# motherpetit.net
KiCad netlist of a schematic drawn in Altium Designer
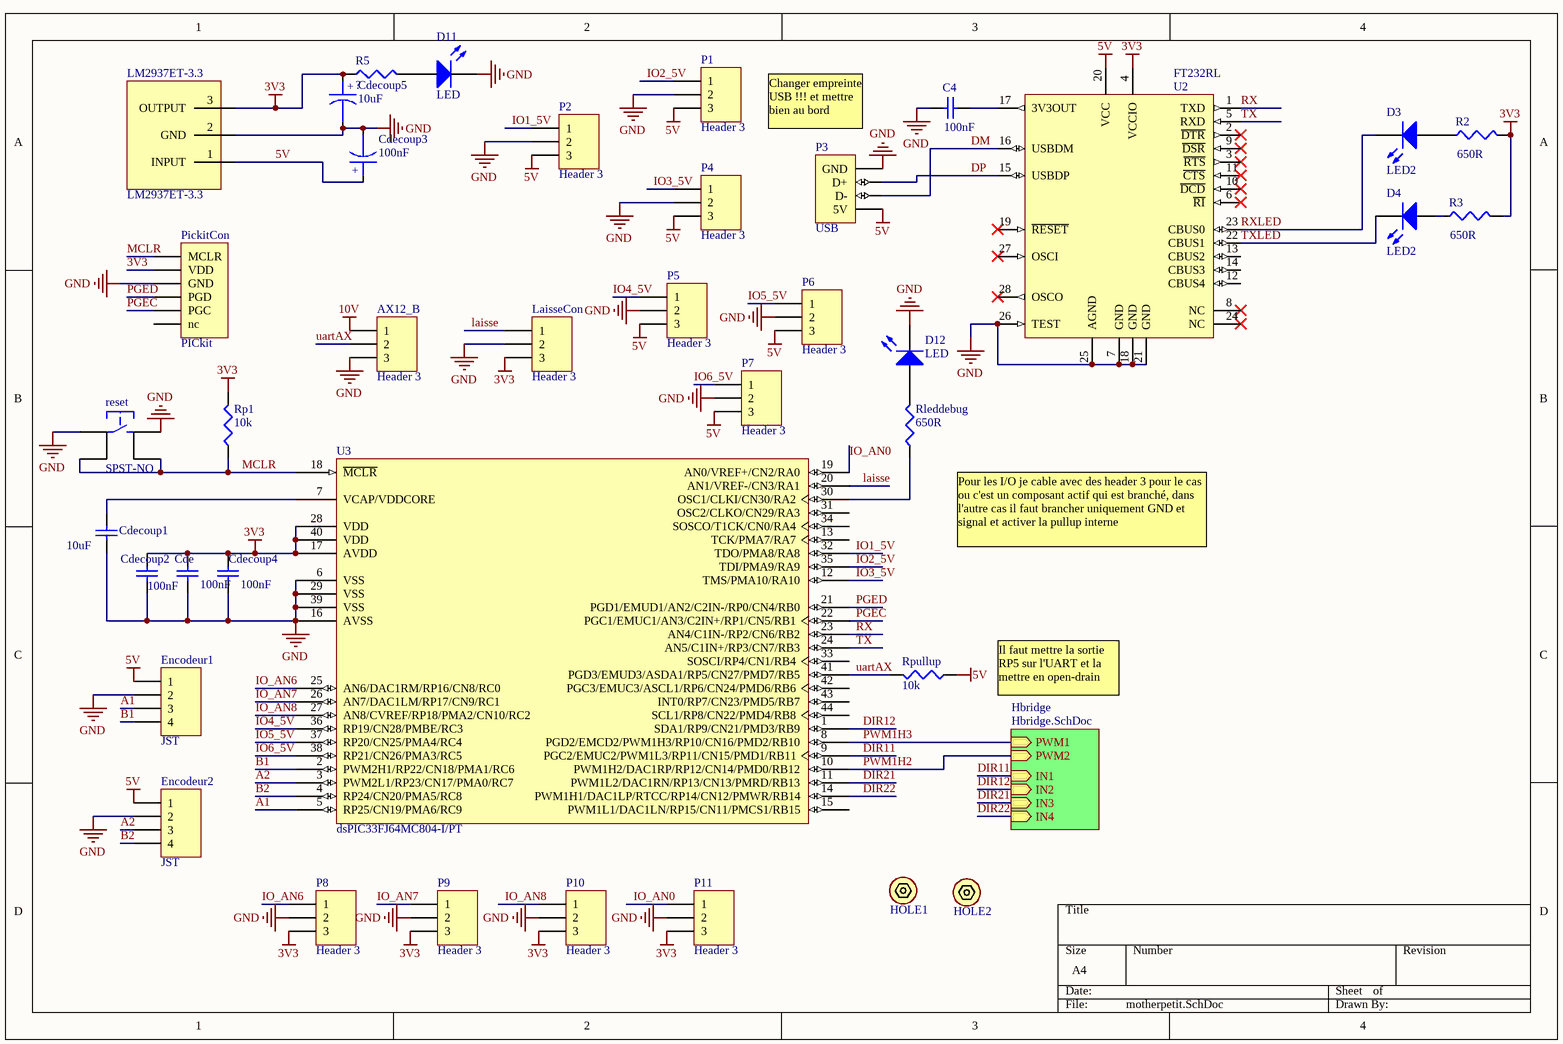
[diagram p0: motherpetit.SchDoc]

(export (version "E")
  (design (tool "Eeschema 10.0.6"))
  (components
    (comp (ref "AX12_B")
      (value "Header 3")
      (footprint "HDR1X3")
      (description "Header, 3-Pin")
      (fields (field (name "PUBLISHER") "Altium Limited"))
      (libsource (lib "7Robot") (part "Header 3"))
    )
    (comp (ref "C4")
      (value "100nF")
      (footprint "C0805C")
      (description "Capacitor (Semiconductor SIM Model)")
      (fields (field (name "PUBLISHER") "Altium Limited"))
      (libsource (lib "Miscellaneous Devices") (part "Cap Semi"))
    )
    (comp (ref "Cde")
      (value "100nF")
      (footprint "C0805C")
      (description "Capacitor")
      (fields (field (name "Comment") "CAP") (field (name "PUBLISHER") "Altium Limited"))
      (libsource (lib "7Robot") (part "CAP"))
    )
    (comp (ref "Cdecoup1")
      (value "10uF")
      (footprint "C0805C")
      (description "Capacitor")
      (fields (field (name "Comment") "CAP") (field (name "PUBLISHER") "Altium Limited"))
      (libsource (lib "7Robot") (part "CAP"))
    )
    (comp (ref "Cdecoup2")
      (value "100nF")
      (footprint "C0805C")
      (description "Capacitor")
      (fields (field (name "Comment") "CAP") (field (name "PUBLISHER") "Altium Limited"))
      (libsource (lib "7Robot") (part "CAP"))
    )
    (comp (ref "Cdecoup3")
      (value "100nF")
      (footprint "RB.1/.3")
      (description "Polarized Capacitor")
      (fields (field (name "Comment") "CAP Pol"))
      (libsource (lib "7Robot") (part "CAP Pol"))
    )
    (comp (ref "Cdecoup4")
      (value "100nF")
      (footprint "C0805C")
      (description "Capacitor")
      (fields (field (name "Comment") "CAP") (field (name "PUBLISHER") "Altium Limited"))
      (libsource (lib "7Robot") (part "CAP"))
    )
    (comp (ref "Cdecoup5")
      (value "10uF")
      (footprint "RB.1/.3")
      (description "Polarized Capacitor")
      (fields (field (name "Comment") "CAP Pol"))
      (libsource (lib "7Robot") (part "CAP Pol"))
    )
    (comp (ref "D3")
      (value "LED2")
      (footprint "LED1206Y")
      (description "Typical RED, GREEN, YELLOW, AMBER GaAs LED")
      (fields (field (name "PUBLISHER") "Altium Limited"))
      (libsource (lib "7Robot") (part "LED2"))
    )
    (comp (ref "D4")
      (value "LED2")
      (footprint "LED1206Y")
      (description "Typical RED, GREEN, YELLOW, AMBER GaAs LED")
      (fields (field (name "PUBLISHER") "Altium Limited"))
      (libsource (lib "7Robot") (part "LED2"))
    )
    (comp (ref "D11")
      (value "LED")
      (footprint "LED1206R")
      (description "Typical LED")
      (fields (field (name "PUBLISHER") "Altium Limited"))
      (libsource (lib "7Robot") (part "LED"))
    )
    (comp (ref "D12")
      (value "LED")
      (footprint "LED1206G")
      (description "Typical LED")
      (fields (field (name "PUBLISHER") "Altium Limited"))
      (libsource (lib "7Robot") (part "LED"))
    )
    (comp (ref "Encodeur1")
      (value "JST")
      (footprint "B4B-PH-K-S")
      (description "Header, 4-Pin")
      (fields (field (name "PUBLISHER") "Altium Limited"))
      (libsource (lib "Miscellaneous Connectors") (part "Header 4"))
    )
    (comp (ref "Encodeur2")
      (value "JST")
      (footprint "B4B-PH-K-S")
      (description "Header, 4-Pin")
      (fields (field (name "PUBLISHER") "Altium Limited"))
      (libsource (lib "Miscellaneous Connectors") (part "Header 4"))
    )
    (comp (ref "HOLE1")
      (value "Hole")
      (footprint "SCREW")
      (description "Mounting Hole for screws")
      (libsource (lib "7Robot") (part "Hole"))
    )
    (comp (ref "HOLE2")
      (value "Hole")
      (footprint "SCREW")
      (description "Mounting Hole for screws")
      (libsource (lib "7Robot") (part "Hole"))
    )
    (comp (ref "LaisseCon")
      (value "Header 3")
      (footprint "HDR1X3")
      (description "Header, 3-Pin")
      (fields (field (name "PUBLISHER") "Altium Limited"))
      (libsource (lib "7Robot") (part "Header 3"))
    )
    (comp (ref "LM2937ET-3.3")
      (value "LM2937ET-3.3")
      (footprint "TO-220V")
      (description "3.3V linear Regulator")
      (libsource (lib "LM293733") (part "LM2937ET-3.3"))
    )
    (comp (ref "P1")
      (value "Header 3")
      (footprint "HDR1X3")
      (description "Header, 3-Pin")
      (fields (field (name "PUBLISHER") "Altium Limited"))
      (libsource (lib "7Robot") (part "Header 3"))
    )
    (comp (ref "P2")
      (value "Header 3")
      (footprint "HDR1X3")
      (description "Header, 3-Pin")
      (fields (field (name "PUBLISHER") "Altium Limited"))
      (libsource (lib "7Robot") (part "Header 3"))
    )
    (comp (ref "P3")
      (value "USB")
      (footprint "USB/SM0.8-4H5")
      (description "USB Connector")
      (fields (field (name "PUBLISHER") "Altium Limited"))
      (libsource (lib "7Robot") (part "USB Con"))
    )
    (comp (ref "P4")
      (value "Header 3")
      (footprint "HDR1X3")
      (description "Header, 3-Pin")
      (fields (field (name "PUBLISHER") "Altium Limited"))
      (libsource (lib "7Robot") (part "Header 3"))
    )
    (comp (ref "P5")
      (value "Header 3")
      (footprint "HDR1X3")
      (description "Header, 3-Pin")
      (fields (field (name "PUBLISHER") "Altium Limited"))
      (libsource (lib "7Robot") (part "Header 3"))
    )
    (comp (ref "P6")
      (value "Header 3")
      (footprint "HDR1X3")
      (description "Header, 3-Pin")
      (fields (field (name "PUBLISHER") "Altium Limited"))
      (libsource (lib "7Robot") (part "Header 3"))
    )
    (comp (ref "P7")
      (value "Header 3")
      (footprint "HDR1X3")
      (description "Header, 3-Pin")
      (fields (field (name "PUBLISHER") "Altium Limited"))
      (libsource (lib "7Robot") (part "Header 3"))
    )
    (comp (ref "P8")
      (value "Header 3")
      (footprint "HDR1X3")
      (description "Header, 3-Pin")
      (fields (field (name "PUBLISHER") "Altium Limited"))
      (libsource (lib "7Robot") (part "Header 3"))
    )
    (comp (ref "P9")
      (value "Header 3")
      (footprint "HDR1X3")
      (description "Header, 3-Pin")
      (fields (field (name "PUBLISHER") "Altium Limited"))
      (libsource (lib "7Robot") (part "Header 3"))
    )
    (comp (ref "P10")
      (value "Header 3")
      (footprint "HDR1X3")
      (description "Header, 3-Pin")
      (fields (field (name "PUBLISHER") "Altium Limited"))
      (libsource (lib "7Robot") (part "Header 3"))
    )
    (comp (ref "P11")
      (value "Header 3")
      (footprint "HDR1X3")
      (description "Header, 3-Pin")
      (fields (field (name "PUBLISHER") "Altium Limited"))
      (libsource (lib "7Robot") (part "Header 3"))
    )
    (comp (ref "PickitCon")
      (value "PICkit")
      (footprint "HDR1X6H")
      (description "Header, 6-Pin, Right Angle")
      (fields (field (name "PUBLISHER") "Altium Limited"))
      (libsource (lib "7Robot") (part "Header ICSP"))
    )
    (comp (ref "R2")
      (value "650R")
      (footprint "C0805R")
      (description "Resistor")
      (fields (field (name "PUBLISHER") "Altium Limited"))
      (libsource (lib "Miscellaneous Devices") (part "Res3"))
    )
    (comp (ref "R3")
      (value "650R")
      (footprint "C0805R")
      (description "Resistor")
      (fields (field (name "PUBLISHER") "Altium Limited"))
      (libsource (lib "Miscellaneous Devices") (part "Res3"))
    )
    (comp (ref "R5")
      (value "?")
      (footprint "C0805R")
      (description "Resistor")
      (fields (field (name "Comment") "RES") (field (name "PUBLISHER") "Altium Limited"))
      (libsource (lib "7Robot") (part "RES"))
    )
    (comp (ref "reset")
      (value "SPST-NO")
      (footprint "SPST-NO")
      (description "Tactile Switch 7.3mm, SMD")
      (libsource (lib "7Robot") (part "SPST-NO"))
    )
    (comp (ref "Rleddebug")
      (value "650R")
      (footprint "C0805R")
      (description "Resistor")
      (fields (field (name "PUBLISHER") "Altium Limited"))
      (libsource (lib "Miscellaneous Devices") (part "Res3"))
    )
    (comp (ref "Rp1")
      (value "10k")
      (footprint "C0805R")
      (description "Resistor")
      (fields (field (name "Comment") "RES") (field (name "PUBLISHER") "Altium Limited"))
      (libsource (lib "7Robot") (part "RES"))
    )
    (comp (ref "Rpullup")
      (value "10k")
      (footprint "C0805R")
      (description "Resistor")
      (fields (field (name "Comment") "RES") (field (name "PUBLISHER") "Altium Limited"))
      (libsource (lib "7Robot") (part "RES"))
    )
    (comp (ref "U2")
      (value "FT232RL")
      (footprint "SSOP-28_M")
      (description "USB UART Asynchronous Serial Data Transfer Chip, SSOP-28, Tube")
      (fields (field (name "PUBLISHER") "Altium Limited"))
      (libsource (lib "7Robot") (part "FT232RL"))
    )
    (comp (ref "U3")
      (value "dsPIC33FJ64MC804-I/PT")
      (footprint "TQFP-PT44_N")
      (fields (field (name "PUBLISHER") "Altium Limited"))
      (libsource (lib "7Robot") (part "dsPIC33FJ64MC804-I/PT"))
    )
  )
  (nets
    (net (code "1") (name "/A1") (class "Default")
      (node (ref "Encodeur1") (pin "3") (pinfunction "3_3") (pintype "passive"))
      (node (ref "U3") (pin "5") (pinfunction "RP25/CN19/PMA6/RC9_5") (pintype "bidirectional"))
    )
    (net (code "2") (name "/A2") (class "Default")
      (node (ref "Encodeur2") (pin "3") (pinfunction "3_3") (pintype "passive"))
      (node (ref "U3") (pin "3") (pinfunction "PWM2L1/RP23/CN17/PMA0/RC7_3") (pintype "bidirectional"))
    )
    (net (code "3") (name "/B1") (class "Default")
      (node (ref "Encodeur1") (pin "4") (pinfunction "4_4") (pintype "passive"))
      (node (ref "U3") (pin "2") (pinfunction "PWM2H1/RP22/CN18/PMA1/RC6_2") (pintype "bidirectional"))
    )
    (net (code "4") (name "/B2") (class "Default")
      (node (ref "Encodeur2") (pin "4") (pinfunction "4_4") (pintype "passive"))
      (node (ref "U3") (pin "4") (pinfunction "RP24/CN20/PMA5/RC8_4") (pintype "bidirectional"))
    )
    (net (code "5") (name "/DIR11") (class "Default")
      (node (ref "U3") (pin "9") (pinfunction "PGC2/EMUC2/PWM1L3/RP11/CN15/PMD1/RB11_9") (pintype "bidirectional"))
    )
    (net (code "6") (name "/DIR12") (class "Default")
      (node (ref "U3") (pin "1") (pinfunction "SDA1/RP9/CN21/PMD3/RB9_1") (pintype "bidirectional"))
    )
    (net (code "7") (name "/DIR21") (class "Default")
      (node (ref "U3") (pin "11") (pinfunction "PWM1L2/DAC1RN/RP13/CN13/PMRD/RB13_11") (pintype "bidirectional"))
    )
    (net (code "8") (name "/DIR22") (class "Default")
      (node (ref "U3") (pin "14") (pinfunction "PWM1H1/DAC1LP/RTCC/RP14/CN12/PMWR/RB14_14") (pintype "bidirectional"))
    )
    (net (code "9") (name "/DM") (class "Default")
      (node (ref "P3") (pin "2") (pinfunction "D-_2") (pintype "bidirectional"))
      (node (ref "U2") (pin "16") (pinfunction "USBDM_16") (pintype "bidirectional"))
    )
    (net (code "10") (name "/DP") (class "Default")
      (node (ref "P3") (pin "3") (pinfunction "D+_3") (pintype "bidirectional"))
      (node (ref "U2") (pin "15") (pinfunction "USBDP_15") (pintype "bidirectional"))
    )
    (net (code "11") (name "/IO1_5V") (class "Default")
      (node (ref "P2") (pin "1") (pinfunction "1_1") (pintype "passive"))
      (node (ref "U3") (pin "32") (pinfunction "TDO/PMA8/RA8_32") (pintype "bidirectional"))
    )
    (net (code "12") (name "/IO2_5V") (class "Default")
      (node (ref "P1") (pin "1") (pinfunction "1_1") (pintype "passive"))
      (node (ref "U3") (pin "35") (pinfunction "TDI/PMA9/RA9_35") (pintype "bidirectional"))
    )
    (net (code "13") (name "/IO3_5V") (class "Default")
      (node (ref "P4") (pin "1") (pinfunction "1_1") (pintype "passive"))
      (node (ref "U3") (pin "12") (pinfunction "TMS/PMA10/RA10_12") (pintype "bidirectional"))
    )
    (net (code "14") (name "/IO4_5V") (class "Default")
      (node (ref "P5") (pin "1") (pinfunction "1_1") (pintype "passive"))
      (node (ref "U3") (pin "36") (pinfunction "RP19/CN28/PMBE/RC3_36") (pintype "bidirectional"))
    )
    (net (code "15") (name "/IO5_5V") (class "Default")
      (node (ref "P6") (pin "1") (pinfunction "1_1") (pintype "passive"))
      (node (ref "U3") (pin "37") (pinfunction "RP20/CN25/PMA4/RC4_37") (pintype "bidirectional"))
    )
    (net (code "16") (name "/IO6_5V") (class "Default")
      (node (ref "P7") (pin "1") (pinfunction "1_1") (pintype "passive"))
      (node (ref "U3") (pin "38") (pinfunction "RP21/CN26/PMA3/RC5_38") (pintype "bidirectional"))
    )
    (net (code "17") (name "/IO_AN0") (class "Default")
      (node (ref "P11") (pin "1") (pinfunction "1_1") (pintype "passive"))
      (node (ref "U3") (pin "19") (pinfunction "AN0/VREF+/CN2/RA0_19") (pintype "bidirectional"))
    )
    (net (code "18") (name "/IO_AN6") (class "Default")
      (node (ref "P8") (pin "1") (pinfunction "1_1") (pintype "passive"))
      (node (ref "U3") (pin "25") (pinfunction "AN6/DAC1RM/RP16/CN8/RC0_25") (pintype "bidirectional"))
    )
    (net (code "19") (name "/IO_AN7") (class "Default")
      (node (ref "P9") (pin "1") (pinfunction "1_1") (pintype "passive"))
      (node (ref "U3") (pin "26") (pinfunction "AN7/DAC1LM/RP17/CN9/RC1_26") (pintype "bidirectional"))
    )
    (net (code "20") (name "/IO_AN8") (class "Default")
      (node (ref "P10") (pin "1") (pinfunction "1_1") (pintype "passive"))
      (node (ref "U3") (pin "27") (pinfunction "AN8/CVREF/RP18/PMA2/CN10/RC2_27") (pintype "bidirectional"))
    )
    (net (code "21") (name "/MCLR") (class "Default")
      (node (ref "PickitCon") (pin "1") (pinfunction "MCLR_1") (pintype "passive"))
      (node (ref "Rp1") (pin "1") (pinfunction "1_1") (pintype "passive"))
      (node (ref "U3") (pin "18") (pinfunction "~{MCLR}_18") (pintype "input"))
      (node (ref "reset") (pin "2") (pintype "passive"))
      (node (ref "reset") (pin "3") (pintype "passive"))
    )
    (net (code "22") (name "/PGEC") (class "Default")
      (node (ref "PickitCon") (pin "5") (pinfunction "PGC_5") (pintype "passive"))
      (node (ref "U3") (pin "22") (pinfunction "PGC1/EMUC1/AN3/C2IN+/RP1/CN5/RB1_22") (pintype "bidirectional"))
    )
    (net (code "23") (name "/PGED") (class "Default")
      (node (ref "PickitCon") (pin "4") (pinfunction "PGD_4") (pintype "passive"))
      (node (ref "U3") (pin "21") (pinfunction "PGD1/EMUD1/AN2/C2IN-/RP0/CN4/RB0_21") (pintype "bidirectional"))
    )
    (net (code "24") (name "/PWM1H2") (class "Default")
      (node (ref "U3") (pin "10") (pinfunction "PWM1H2/DAC1RP/RP12/CN14/PMD0/RB12_10") (pintype "bidirectional"))
    )
    (net (code "25") (name "/PWM1H3") (class "Default")
      (node (ref "U3") (pin "8") (pinfunction "PGD2/EMCD2/PWM1H3/RP10/CN16/PMD2/RB10_8") (pintype "bidirectional"))
    )
    (net (code "26") (name "/RX") (class "Default")
      (node (ref "U2") (pin "1") (pinfunction "TXD_1") (pintype "output"))
      (node (ref "U3") (pin "23") (pinfunction "AN4/C1IN-/RP2/CN6/RB2_23") (pintype "bidirectional"))
    )
    (net (code "27") (name "/RXLED") (class "Default")
      (node (ref "D3") (pin "2") (pinfunction "K_2") (pintype "passive"))
      (node (ref "U2") (pin "23") (pinfunction "CBUS0_23") (pintype "bidirectional"))
    )
    (net (code "28") (name "/TX") (class "Default")
      (node (ref "U2") (pin "5") (pinfunction "RXD_5") (pintype "input"))
      (node (ref "U3") (pin "24") (pinfunction "AN5/C1IN+/RP3/CN7/RB3_24") (pintype "bidirectional"))
    )
    (net (code "29") (name "/TXLED") (class "Default")
      (node (ref "D4") (pin "2") (pinfunction "K_2") (pintype "passive"))
      (node (ref "U2") (pin "22") (pinfunction "CBUS1_22") (pintype "bidirectional"))
    )
    (net (code "30") (name "/laisse") (class "Default")
      (node (ref "LaisseCon") (pin "1") (pinfunction "1_1") (pintype "passive"))
      (node (ref "U3") (pin "20") (pinfunction "AN1/VREF-/CN3/RA1_20") (pintype "bidirectional"))
    )
    (net (code "31") (name "/uartAX") (class "Default")
      (node (ref "AX12_B") (pin "2") (pinfunction "2_2") (pintype "passive"))
      (node (ref "Rpullup") (pin "2") (pinfunction "2_2") (pintype "passive"))
      (node (ref "U3") (pin "41") (pinfunction "PGD3/EMUD3/ASDA1/RP5/CN27/PMD7/RB5_41") (pintype "bidirectional"))
    )
    (net (code "32") (name "3V3") (class "Default")
      (node (ref "Cde") (pin "2") (pinfunction "2_2") (pintype "passive"))
      (node (ref "Cdecoup2") (pin "2") (pinfunction "2_2") (pintype "passive"))
      (node (ref "Cdecoup4") (pin "2") (pinfunction "2_2") (pintype "passive"))
      (node (ref "Cdecoup5") (pin "1") (pinfunction "1_1") (pintype "passive"))
      (node (ref "LM2937ET-3.3") (pin "3") (pinfunction "OUTPUT_3") (pintype "power_in"))
      (node (ref "LaisseCon") (pin "3") (pinfunction "3_3") (pintype "passive"))
      (node (ref "P10") (pin "3") (pinfunction "3_3") (pintype "passive"))
      (node (ref "P11") (pin "3") (pinfunction "3_3") (pintype "passive"))
      (node (ref "P8") (pin "3") (pinfunction "3_3") (pintype "passive"))
      (node (ref "P9") (pin "3") (pinfunction "3_3") (pintype "passive"))
      (node (ref "PickitCon") (pin "2") (pinfunction "VDD_2") (pintype "passive"))
      (node (ref "R2") (pin "2") (pinfunction "2_2") (pintype "passive"))
      (node (ref "R3") (pin "2") (pinfunction "2_2") (pintype "passive"))
      (node (ref "R5") (pin "1") (pinfunction "1_1") (pintype "passive"))
      (node (ref "Rp1") (pin "2") (pinfunction "2_2") (pintype "passive"))
      (node (ref "U2") (pin "4") (pinfunction "VCCIO_4") (pintype "power_in"))
      (node (ref "U3") (pin "17") (pinfunction "AVDD_17") (pintype "power_in"))
      (node (ref "U3") (pin "28") (pinfunction "VDD_28") (pintype "power_in"))
      (node (ref "U3") (pin "40") (pinfunction "VDD_40") (pintype "power_in"))
    )
    (net (code "33") (name "5V") (class "Default")
      (node (ref "Cdecoup3") (pin "1") (pinfunction "1_1") (pintype "passive"))
      (node (ref "Encodeur1") (pin "1") (pinfunction "1_1") (pintype "passive"))
      (node (ref "Encodeur2") (pin "1") (pinfunction "1_1") (pintype "passive"))
      (node (ref "LM2937ET-3.3") (pin "1") (pinfunction "INPUT_1") (pintype "power_in"))
      (node (ref "P1") (pin "3") (pinfunction "3_3") (pintype "passive"))
      (node (ref "P2") (pin "3") (pinfunction "3_3") (pintype "passive"))
      (node (ref "P3") (pin "1") (pinfunction "5V_1") (pintype "power_in"))
      (node (ref "P4") (pin "3") (pinfunction "3_3") (pintype "passive"))
      (node (ref "P5") (pin "3") (pinfunction "3_3") (pintype "passive"))
      (node (ref "P6") (pin "3") (pinfunction "3_3") (pintype "passive"))
      (node (ref "P7") (pin "3") (pinfunction "3_3") (pintype "passive"))
      (node (ref "Rpullup") (pin "1") (pinfunction "1_1") (pintype "passive"))
      (node (ref "U2") (pin "20") (pinfunction "VCC_20") (pintype "power_in"))
    )
    (net (code "34") (name "10V") (class "Default")
      (node (ref "AX12_B") (pin "1") (pinfunction "1_1") (pintype "passive"))
    )
    (net (code "35") (name "GND") (class "Default")
      (node (ref "AX12_B") (pin "3") (pinfunction "3_3") (pintype "passive"))
      (node (ref "C4") (pin "1") (pinfunction "1_1") (pintype "passive"))
      (node (ref "Cde") (pin "1") (pinfunction "1_1") (pintype "passive"))
      (node (ref "Cdecoup1") (pin "1") (pinfunction "1_1") (pintype "passive"))
      (node (ref "Cdecoup2") (pin "1") (pinfunction "1_1") (pintype "passive"))
      (node (ref "Cdecoup3") (pin "2") (pinfunction "2_2") (pintype "passive"))
      (node (ref "Cdecoup4") (pin "1") (pinfunction "1_1") (pintype "passive"))
      (node (ref "Cdecoup5") (pin "2") (pinfunction "2_2") (pintype "passive"))
      (node (ref "D11") (pin "2") (pinfunction "K_2") (pintype "passive"))
      (node (ref "D12") (pin "2") (pinfunction "K_2") (pintype "passive"))
      (node (ref "Encodeur1") (pin "2") (pinfunction "2_2") (pintype "passive"))
      (node (ref "Encodeur2") (pin "2") (pinfunction "2_2") (pintype "passive"))
      (node (ref "LM2937ET-3.3") (pin "2") (pinfunction "GND_2") (pintype "passive"))
      (node (ref "LaisseCon") (pin "2") (pinfunction "2_2") (pintype "passive"))
      (node (ref "P1") (pin "2") (pinfunction "2_2") (pintype "passive"))
      (node (ref "P10") (pin "2") (pinfunction "2_2") (pintype "passive"))
      (node (ref "P11") (pin "2") (pinfunction "2_2") (pintype "passive"))
      (node (ref "P2") (pin "2") (pinfunction "2_2") (pintype "passive"))
      (node (ref "P3") (pin "4") (pinfunction "GND_4") (pintype "power_in"))
      (node (ref "P4") (pin "2") (pinfunction "2_2") (pintype "passive"))
      (node (ref "P5") (pin "2") (pinfunction "2_2") (pintype "passive"))
      (node (ref "P6") (pin "2") (pinfunction "2_2") (pintype "passive"))
      (node (ref "P7") (pin "2") (pinfunction "2_2") (pintype "passive"))
      (node (ref "P8") (pin "2") (pinfunction "2_2") (pintype "passive"))
      (node (ref "P9") (pin "2") (pinfunction "2_2") (pintype "passive"))
      (node (ref "PickitCon") (pin "3") (pinfunction "GND_3") (pintype "passive"))
      (node (ref "U2") (pin "18") (pinfunction "GND_18") (pintype "power_in"))
      (node (ref "U2") (pin "21") (pinfunction "GND_21") (pintype "power_in"))
      (node (ref "U2") (pin "25") (pinfunction "AGND_25") (pintype "power_in"))
      (node (ref "U2") (pin "26") (pinfunction "TEST_26") (pintype "input"))
      (node (ref "U2") (pin "7") (pinfunction "GND_7") (pintype "power_in"))
      (node (ref "U3") (pin "16") (pinfunction "AVSS_16") (pintype "power_in"))
      (node (ref "U3") (pin "29") (pinfunction "VSS_29") (pintype "power_in"))
      (node (ref "U3") (pin "39") (pinfunction "VSS_39") (pintype "power_in"))
      (node (ref "U3") (pin "6") (pinfunction "VSS_6") (pintype "power_in"))
      (node (ref "reset") (pin "1") (pintype "passive"))
      (node (ref "reset") (pin "4") (pintype "passive"))
    )
    (net (code "36") (name "Net-(D3-A)") (class "Default")
      (node (ref "D3") (pin "1") (pinfunction "A_1") (pintype "passive"))
      (node (ref "R2") (pin "1") (pinfunction "1_1") (pintype "passive"))
    )
    (net (code "37") (name "Net-(D4-A)") (class "Default")
      (node (ref "D4") (pin "1") (pinfunction "A_1") (pintype "passive"))
      (node (ref "R3") (pin "1") (pinfunction "1_1") (pintype "passive"))
    )
    (net (code "38") (name "Net-(D11-A)") (class "Default")
      (node (ref "D11") (pin "1") (pinfunction "A_1") (pintype "passive"))
      (node (ref "R5") (pin "2") (pinfunction "2_2") (pintype "passive"))
    )
    (net (code "39") (name "Net-(D12-A)") (class "Default")
      (node (ref "D12") (pin "1") (pinfunction "A_1") (pintype "passive"))
      (node (ref "Rleddebug") (pin "2") (pinfunction "2_2") (pintype "passive"))
    )
    (net (code "40") (name "Net-(U2-3V3OUT)") (class "Default")
      (node (ref "C4") (pin "2") (pinfunction "2_2") (pintype "passive"))
      (node (ref "U2") (pin "17") (pinfunction "3V3OUT_17") (pintype "output"))
    )
    (net (code "41") (name "Net-(U3-OSC1{slash}CLKI{slash}CN30{slash}RA2)") (class "Default")
      (node (ref "Rleddebug") (pin "1") (pinfunction "1_1") (pintype "passive"))
      (node (ref "U3") (pin "30") (pinfunction "OSC1/CLKI/CN30/RA2_30") (pintype "bidirectional"))
    )
    (net (code "42") (name "Net-(U3-VCAP{slash}VDDCORE)") (class "Default")
      (node (ref "Cdecoup1") (pin "2") (pinfunction "2_2") (pintype "passive"))
      (node (ref "U3") (pin "7") (pinfunction "VCAP/VDDCORE_7") (pintype "power_in"))
    )
    (net (code "43") (name "unconnected-(HOLE1-Hole-Pad1)") (class "Default")
      (node (ref "HOLE1") (pin "1") (pinfunction "Hole_1") (pintype "passive"))
    )
    (net (code "44") (name "unconnected-(HOLE2-Hole-Pad1)") (class "Default")
      (node (ref "HOLE2") (pin "1") (pinfunction "Hole_1") (pintype "passive"))
    )
    (net (code "45") (name "unconnected-(PickitCon-nc-Pad6)") (class "Default")
      (node (ref "PickitCon") (pin "6") (pinfunction "nc_6") (pintype "passive"))
    )
    (net (code "46") (name "unconnected-(U2-CBUS2-Pad13)") (class "Default")
      (node (ref "U2") (pin "13") (pinfunction "CBUS2_13") (pintype "bidirectional"))
    )
    (net (code "47") (name "unconnected-(U2-CBUS3-Pad14)") (class "Default")
      (node (ref "U2") (pin "14") (pinfunction "CBUS3_14") (pintype "bidirectional"))
    )
    (net (code "48") (name "unconnected-(U2-CBUS4-Pad12)") (class "Default")
      (node (ref "U2") (pin "12") (pinfunction "CBUS4_12") (pintype "bidirectional"))
    )
    (net (code "49") (name "unconnected-(U2-NC-Pad8)") (class "Default")
      (node (ref "U2") (pin "8") (pinfunction "NC_8") (pintype "passive+no_connect"))
    )
    (net (code "50") (name "unconnected-(U2-NC-Pad24)") (class "Default")
      (node (ref "U2") (pin "24") (pinfunction "NC_24") (pintype "passive+no_connect"))
    )
    (net (code "51") (name "unconnected-(U2-OSCI-Pad27)") (class "Default")
      (node (ref "U2") (pin "27") (pinfunction "OSCI_27") (pintype "input+no_connect"))
    )
    (net (code "52") (name "unconnected-(U2-OSCO-Pad28)") (class "Default")
      (node (ref "U2") (pin "28") (pinfunction "OSCO_28") (pintype "output+no_connect"))
    )
    (net (code "53") (name "unconnected-(U2-~{CTS}-Pad11)") (class "Default")
      (node (ref "U2") (pin "11") (pinfunction "~{CTS}_11") (pintype "input+no_connect"))
    )
    (net (code "54") (name "unconnected-(U2-~{DCD}-Pad10)") (class "Default")
      (node (ref "U2") (pin "10") (pinfunction "~{DCD}_10") (pintype "input+no_connect"))
    )
    (net (code "55") (name "unconnected-(U2-~{DSR}-Pad9)") (class "Default")
      (node (ref "U2") (pin "9") (pinfunction "~{DSR}_9") (pintype "input+no_connect"))
    )
    (net (code "56") (name "unconnected-(U2-~{DTR}-Pad2)") (class "Default")
      (node (ref "U2") (pin "2") (pinfunction "~{DTR}_2") (pintype "output+no_connect"))
    )
    (net (code "57") (name "unconnected-(U2-~{RESET}-Pad19)") (class "Default")
      (node (ref "U2") (pin "19") (pinfunction "~{RESET}_19") (pintype "input+no_connect"))
    )
    (net (code "58") (name "unconnected-(U2-~{RI}-Pad6)") (class "Default")
      (node (ref "U2") (pin "6") (pinfunction "~{RI}_6") (pintype "input+no_connect"))
    )
    (net (code "59") (name "unconnected-(U2-~{RTS}-Pad3)") (class "Default")
      (node (ref "U2") (pin "3") (pinfunction "~{RTS}_3") (pintype "output+no_connect"))
    )
    (net (code "60") (name "unconnected-(U3-INT0{slash}RP7{slash}CN23{slash}PMD5{slash}RB7-Pad43)") (class "Default")
      (node (ref "U3") (pin "43") (pinfunction "INT0/RP7/CN23/PMD5/RB7_43") (pintype "bidirectional"))
    )
    (net (code "61") (name "unconnected-(U3-OSC2{slash}CLKO{slash}CN29{slash}RA3-Pad31)") (class "Default")
      (node (ref "U3") (pin "31") (pinfunction "OSC2/CLKO/CN29/RA3_31") (pintype "bidirectional"))
    )
    (net (code "62") (name "unconnected-(U3-PGC3{slash}EMUC3{slash}ASCL1{slash}RP6{slash}CN24{slash}PMD6{slash}RB6-Pad42)") (class "Default")
      (node (ref "U3") (pin "42") (pinfunction "PGC3/EMUC3/ASCL1/RP6/CN24/PMD6/RB6_42") (pintype "bidirectional"))
    )
    (net (code "63") (name "unconnected-(U3-PWM1L1{slash}DAC1LN{slash}RP15{slash}CN11{slash}PMCS1{slash}RB15-Pad15)") (class "Default")
      (node (ref "U3") (pin "15") (pinfunction "PWM1L1/DAC1LN/RP15/CN11/PMCS1/RB15_15") (pintype "bidirectional"))
    )
    (net (code "64") (name "unconnected-(U3-SCL1{slash}RP8{slash}CN22{slash}PMD4{slash}RB8-Pad44)") (class "Default")
      (node (ref "U3") (pin "44") (pinfunction "SCL1/RP8/CN22/PMD4/RB8_44") (pintype "bidirectional"))
    )
    (net (code "65") (name "unconnected-(U3-SOSCI{slash}RP4{slash}CN1{slash}RB4-Pad33)") (class "Default")
      (node (ref "U3") (pin "33") (pinfunction "SOSCI/RP4/CN1/RB4_33") (pintype "bidirectional"))
    )
    (net (code "66") (name "unconnected-(U3-SOSCO{slash}T1CK{slash}CN0{slash}RA4-Pad34)") (class "Default")
      (node (ref "U3") (pin "34") (pinfunction "SOSCO/T1CK/CN0/RA4_34") (pintype "bidirectional"))
    )
    (net (code "67") (name "unconnected-(U3-TCK{slash}PMA7{slash}RA7-Pad13)") (class "Default")
      (node (ref "U3") (pin "13") (pinfunction "TCK/PMA7/RA7_13") (pintype "bidirectional"))
    )
  )
)
